# firealarm1.net
KiCad netlist of a schematic drawn in EAGLE
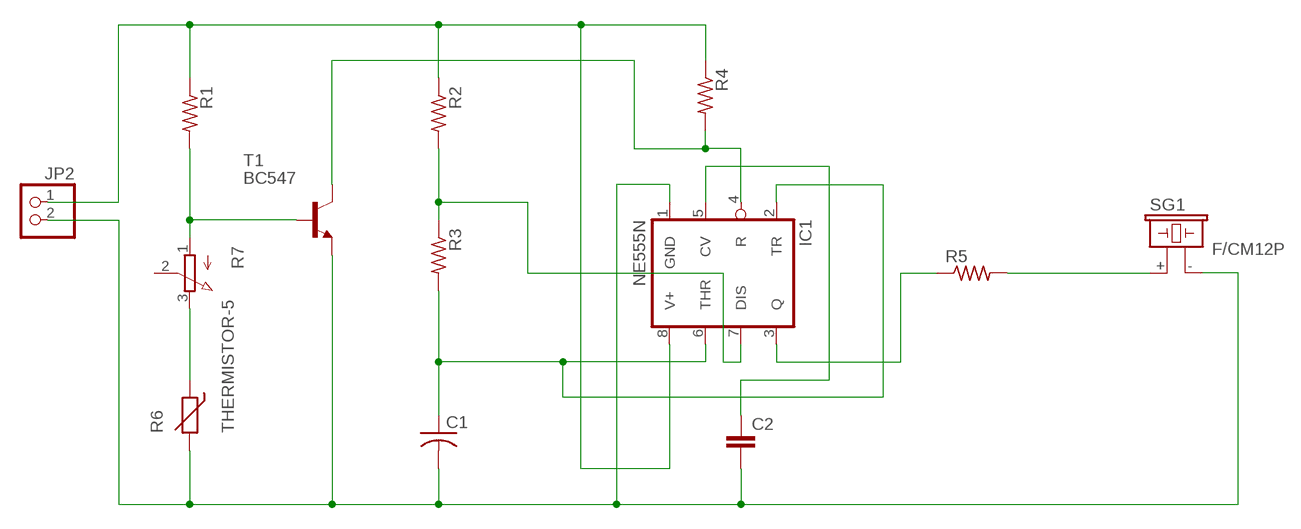
[diagram p0: schematic, sheet 1]

(export (version "E")
  (design (tool "Eeschema 10.0.6"))
  (components
    (comp (ref "C1")
      (value "C-US050-025X075")
      (footprint "eagle-import:C050-025X075")
      (libsource (lib "eagle-import") (part "C-US050-025X075"))
    )
    (comp (ref "C2")
      (value "C-EU025-025X050")
      (footprint "eagle-import:C025-025X050")
      (libsource (lib "eagle-import") (part "C-EU025-025X050"))
    )
    (comp (ref "IC1")
      (value "NE555N")
      (footprint "eagle-import:DIL08")
      (libsource (lib "eagle-import") (part "555NNE"))
    )
    (comp (ref "JP2")
      (value "PINHD-1X2")
      (footprint "eagle-import:1X02")
      (libsource (lib "eagle-import") (part "PINHD-1X2"))
    )
    (comp (ref "R1")
      (value "R-US_0207/10")
      (footprint "eagle-import:0207_10")
      (libsource (lib "eagle-import") (part "R-US_0207/10"))
    )
    (comp (ref "R2")
      (value "R-US_0207/10")
      (footprint "eagle-import:0207_10")
      (libsource (lib "eagle-import") (part "R-US_0207/10"))
    )
    (comp (ref "R3")
      (value "R-US_0207/10")
      (footprint "eagle-import:0207_10")
      (libsource (lib "eagle-import") (part "R-US_0207/10"))
    )
    (comp (ref "R4")
      (value "R-US_0207/10")
      (footprint "eagle-import:0207_10")
      (libsource (lib "eagle-import") (part "R-US_0207/10"))
    )
    (comp (ref "R5")
      (value "R-US_0207/10")
      (footprint "eagle-import:0207_10")
      (libsource (lib "eagle-import") (part "R-US_0207/10"))
    )
    (comp (ref "R6")
      (value "THERMISTOR-5")
      (footprint "eagle-import:R-5")
      (libsource (lib "eagle-import") (part "THERMISTOR-5"))
    )
    (comp (ref "R7")
      (value "3RP/1610N")
      (footprint "eagle-import:3RP_1610N")
      (libsource (lib "eagle-import") (part "3RP/1610N"))
    )
    (comp (ref "SG1")
      (value "F/CM12P")
      (footprint "eagle-import:F_CM12P")
      (libsource (lib "eagle-import") (part "F/CM12P"))
    )
    (comp (ref "T1")
      (value "BC547")
      (footprint "eagle-import:TO92")
      (libsource (lib "eagle-import") (part "BC547"))
    )
  )
  (nets
    (net (code "1") (name "Net-(IC1-CV)") (class "Default")
      (node (ref "C2") (pin "1") (pinfunction "1_1") (pintype "passive"))
      (node (ref "IC1") (pin "5") (pinfunction "CV_5") (pintype "input"))
    )
    (net (code "2") (name "Net-(IC1-DIS)") (class "Default")
      (node (ref "IC1") (pin "7") (pinfunction "DIS_7") (pintype "input"))
      (node (ref "R2") (pin "2") (pinfunction "2_2") (pintype "passive"))
      (node (ref "R3") (pin "1") (pinfunction "1_1") (pintype "passive"))
    )
    (net (code "3") (name "Net-(IC1-GND)") (class "Default")
      (node (ref "C1") (pin "2") (pinfunction "2_2") (pintype "passive"))
      (node (ref "C2") (pin "2") (pinfunction "2_2") (pintype "passive"))
      (node (ref "IC1") (pin "1") (pinfunction "GND_1") (pintype "power_in"))
      (node (ref "JP2") (pin "2") (pinfunction "2_2") (pintype "passive"))
      (node (ref "R6") (pin "2") (pinfunction "2_2") (pintype "passive"))
      (node (ref "SG1") (pin "-") (pinfunction "2_-") (pintype "passive"))
      (node (ref "T1") (pin "1") (pinfunction "E_1") (pintype "passive"))
    )
    (net (code "4") (name "Net-(IC1-Q)") (class "Default")
      (node (ref "IC1") (pin "3") (pinfunction "Q_3") (pintype "output"))
      (node (ref "R5") (pin "1") (pinfunction "1_1") (pintype "passive"))
    )
    (net (code "5") (name "Net-(IC1-R)") (class "Default")
      (node (ref "IC1") (pin "4") (pinfunction "R_4") (pintype "input"))
      (node (ref "R4") (pin "2") (pinfunction "2_2") (pintype "passive"))
      (node (ref "T1") (pin "3") (pinfunction "C_3") (pintype "passive"))
    )
    (net (code "6") (name "Net-(IC1-THR)") (class "Default")
      (node (ref "C1") (pin "1") (pinfunction "1_1") (pintype "passive"))
      (node (ref "IC1") (pin "2") (pinfunction "TR_2") (pintype "input"))
      (node (ref "IC1") (pin "6") (pinfunction "THR_6") (pintype "input"))
      (node (ref "R3") (pin "2") (pinfunction "2_2") (pintype "passive"))
    )
    (net (code "7") (name "Net-(IC1-V+)") (class "Default")
      (node (ref "IC1") (pin "8") (pinfunction "V+_8") (pintype "power_in"))
      (node (ref "JP2") (pin "1") (pinfunction "1_1") (pintype "passive"))
      (node (ref "R1") (pin "1") (pinfunction "1_1") (pintype "passive"))
      (node (ref "R2") (pin "1") (pinfunction "1_1") (pintype "passive"))
      (node (ref "R4") (pin "1") (pinfunction "1_1") (pintype "passive"))
    )
    (net (code "8") (name "Net-(R7-A)") (class "Default")
      (node (ref "R1") (pin "2") (pinfunction "2_2") (pintype "passive"))
      (node (ref "R7") (pin "1") (pinfunction "A_1") (pintype "passive"))
      (node (ref "T1") (pin "2") (pinfunction "B_2") (pintype "passive"))
    )
    (net (code "9") (name "Net-(R7-E)") (class "Default")
      (node (ref "R6") (pin "1") (pinfunction "1_1") (pintype "passive"))
      (node (ref "R7") (pin "3") (pinfunction "E_3") (pintype "passive"))
    )
    (net (code "10") (name "Net-(SG1-1)") (class "Default")
      (node (ref "R5") (pin "2") (pinfunction "2_2") (pintype "passive"))
      (node (ref "SG1") (pin "+") (pinfunction "1_+") (pintype "passive"))
    )
    (net (code "11") (name "unconnected-(R7-S-Pad2)") (class "Default")
      (node (ref "R7") (pin "2") (pinfunction "S_2") (pintype "passive"))
    )
  )
)
